# DDR4_SODIMM2.net
KiCad netlist of a schematic drawn in Altium Designer
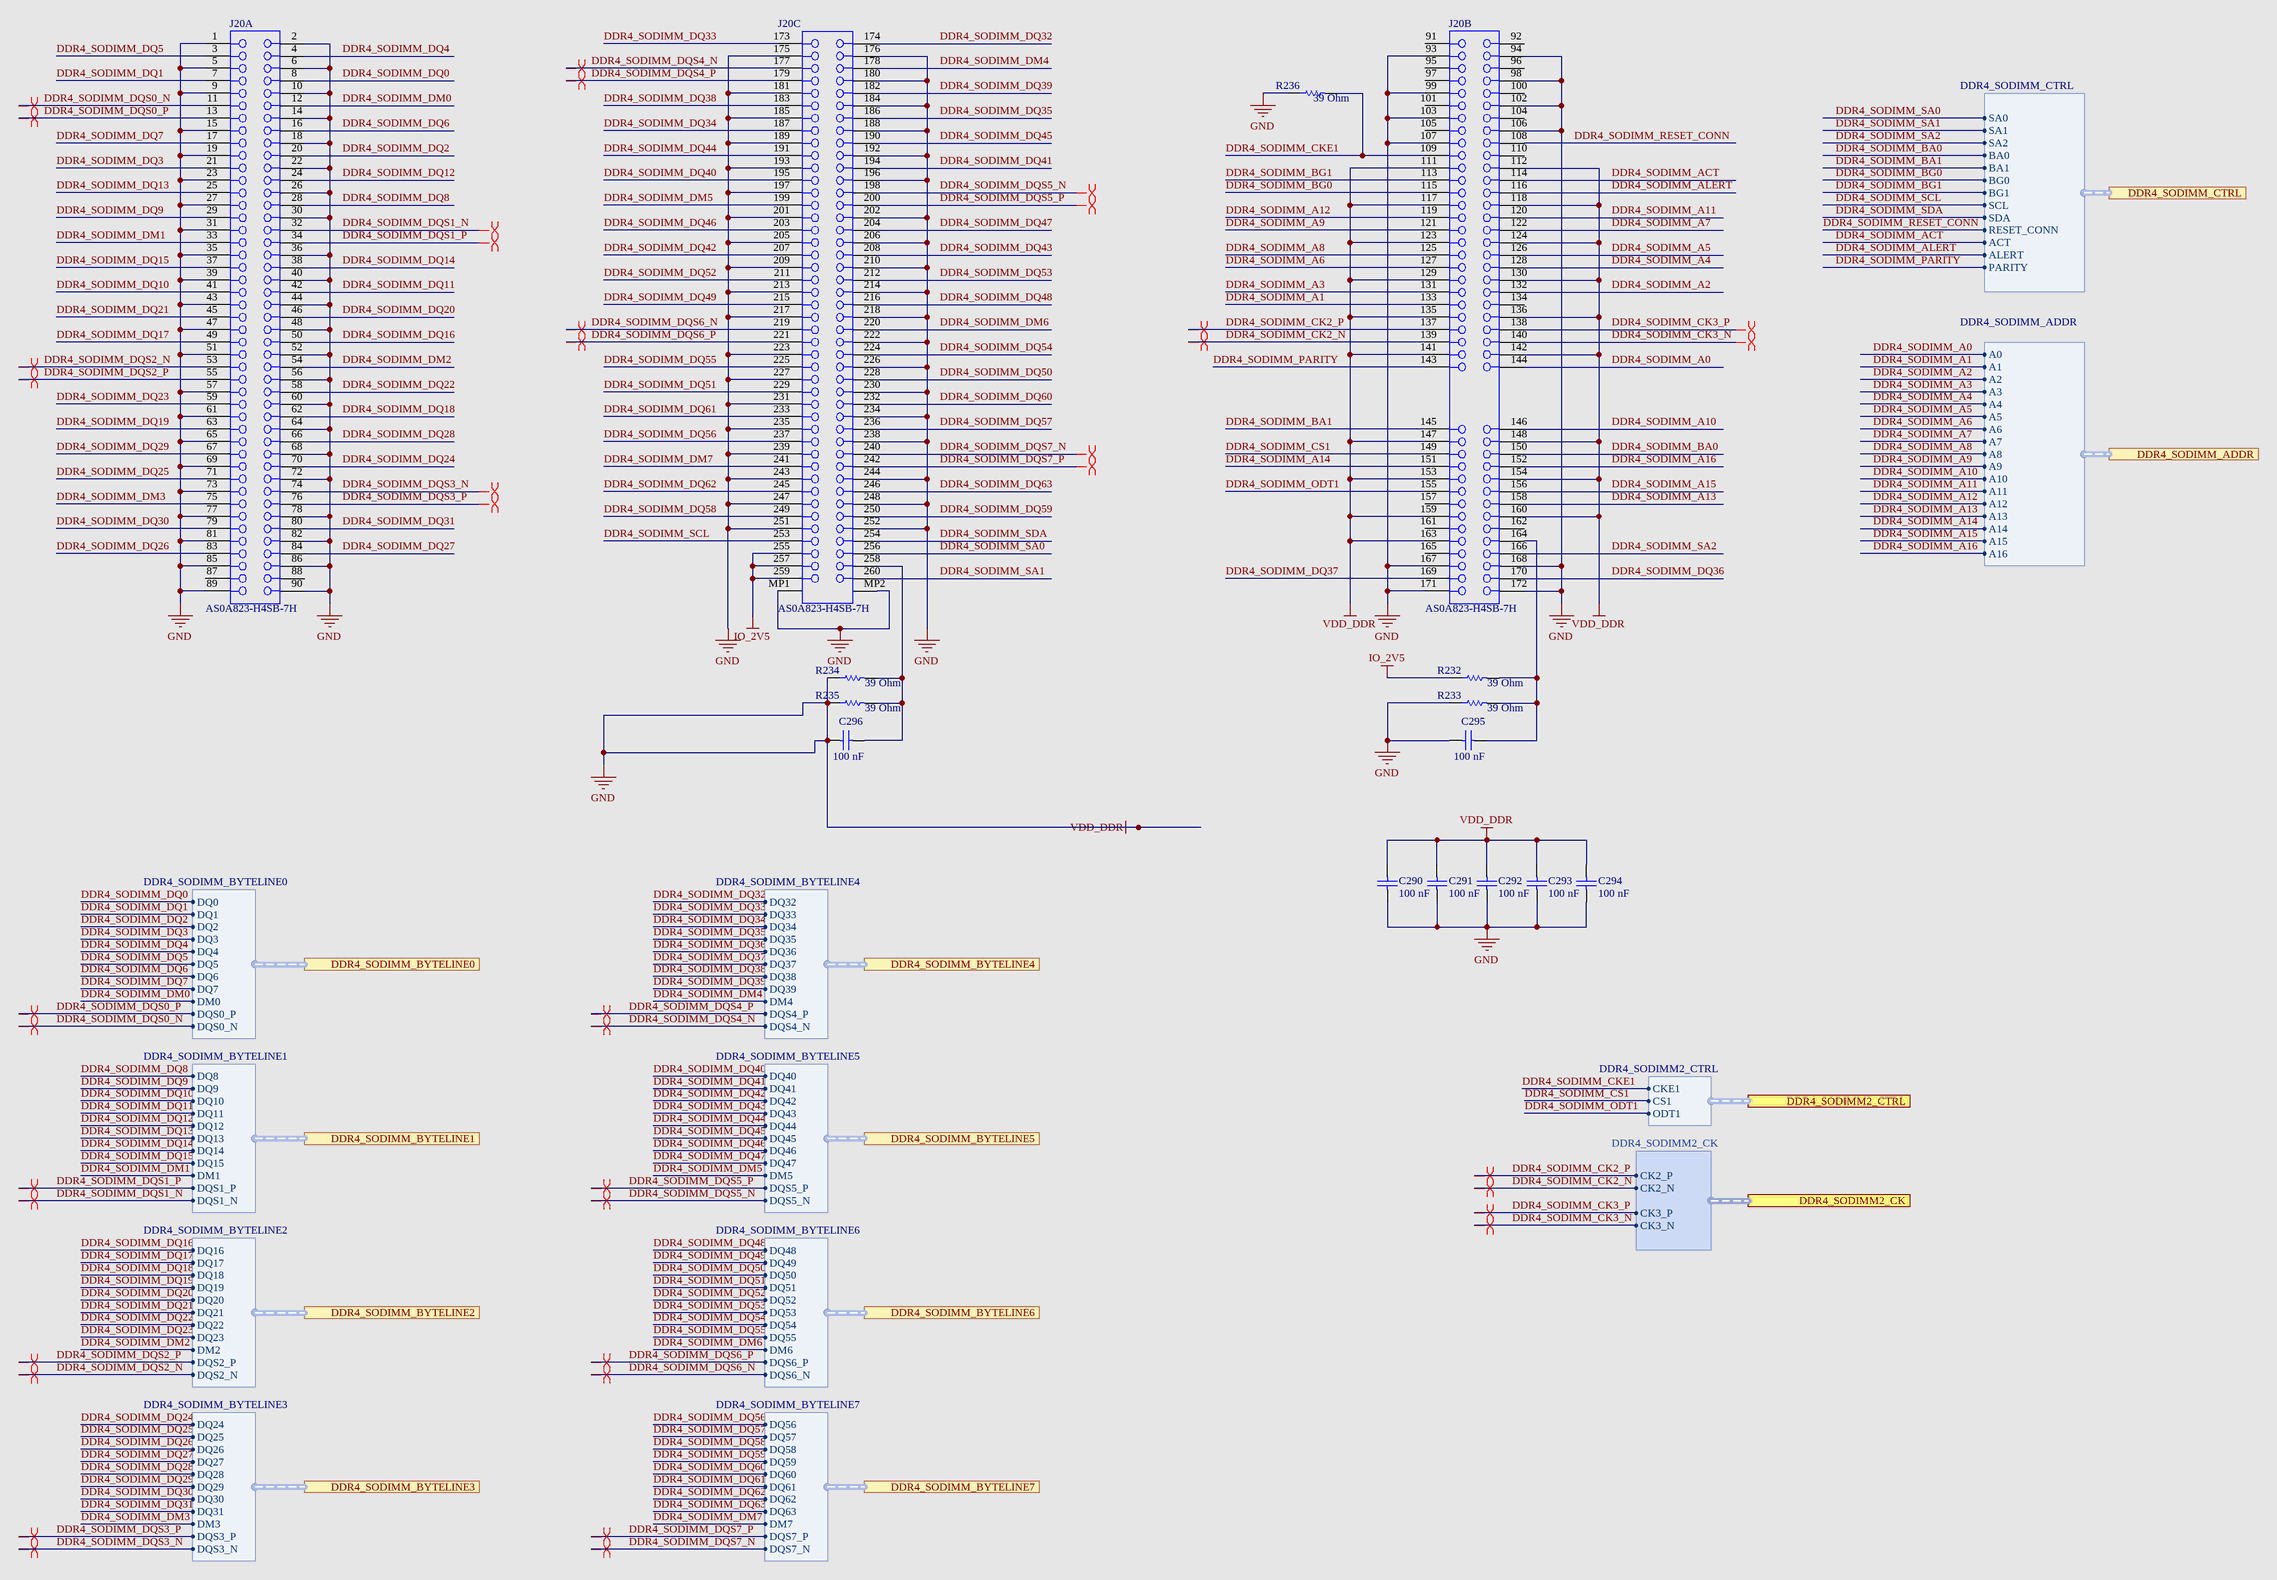
[diagram p0: DDR4_SODIMM2.SchDoc]

(export (version "E")
  (design (tool "Eeschema 10.0.6"))
  (components
    (comp (ref "C290")
      (value "C1005X7R1E104M")
      (footprint "CAPC1005X55X10LL05")
      (description "Chip Capacitor, 0.1 uF, +/- 20%, 25 V, -55 to 125 degC, 0402 (1005 Metric), RoHS, Tape and Reel")
      (fields (field (name "TOLERANCE") "20%") (field (name "CAPACITANCE") "100 nF"))
      (libsource (lib "Altium Content Vault") (part "CAP-NP-2"))
    )
    (comp (ref "C291")
      (value "C1005X7R1E104M")
      (footprint "CAPC1005X55X10LL05")
      (description "Chip Capacitor, 0.1 uF, +/- 20%, 25 V, -55 to 125 degC, 0402 (1005 Metric), RoHS, Tape and Reel")
      (fields (field (name "TOLERANCE") "20%") (field (name "CAPACITANCE") "100 nF"))
      (libsource (lib "Altium Content Vault") (part "CAP-NP-2"))
    )
    (comp (ref "C292")
      (value "C1005X7R1E104M")
      (footprint "CAPC1005X55X10LL05")
      (description "Chip Capacitor, 0.1 uF, +/- 20%, 25 V, -55 to 125 degC, 0402 (1005 Metric), RoHS, Tape and Reel")
      (fields (field (name "TOLERANCE") "20%") (field (name "CAPACITANCE") "100 nF"))
      (libsource (lib "Altium Content Vault") (part "CAP-NP-2"))
    )
    (comp (ref "C293")
      (value "C1005X7R1E104M")
      (footprint "CAPC1005X55X10LL05")
      (description "Chip Capacitor, 0.1 uF, +/- 20%, 25 V, -55 to 125 degC, 0402 (1005 Metric), RoHS, Tape and Reel")
      (fields (field (name "TOLERANCE") "20%") (field (name "CAPACITANCE") "100 nF"))
      (libsource (lib "Altium Content Vault") (part "CAP-NP-2"))
    )
    (comp (ref "C294")
      (value "C1005X7R1E104M")
      (footprint "CAPC1005X55X10LL05")
      (description "Chip Capacitor, 0.1 uF, +/- 20%, 25 V, -55 to 125 degC, 0402 (1005 Metric), RoHS, Tape and Reel")
      (fields (field (name "TOLERANCE") "20%") (field (name "CAPACITANCE") "100 nF"))
      (libsource (lib "Altium Content Vault") (part "CAP-NP-2"))
    )
    (comp (ref "C295")
      (value "C1005X7R1E104M")
      (footprint "CAPC1005X55X10LL05")
      (description "Chip Capacitor, 0.1 uF, +/- 20%, 25 V, -55 to 125 degC, 0402 (1005 Metric), RoHS, Tape and Reel")
      (fields (field (name "TOLERANCE") "20%") (field (name "CAPACITANCE") "100 nF"))
      (libsource (lib "Altium Content Vault") (part "CAP-NP-2"))
    )
    (comp (ref "C296")
      (value "C1005X7R1E104M")
      (footprint "CAPC1005X55X10LL05")
      (description "Chip Capacitor, 0.1 uF, +/- 20%, 25 V, -55 to 125 degC, 0402 (1005 Metric), RoHS, Tape and Reel")
      (fields (field (name "TOLERANCE") "20%") (field (name "CAPACITANCE") "100 nF"))
      (libsource (lib "Altium Content Vault") (part "CAP-NP-2"))
    )
    (comp (ref "J20")
      (value "AS0A823-H4SB-7H")
      (footprint "FOXC-AS0A823-H4SB-7H_V")
      (libsource (lib "Altium Content Vault") (part "CN-2S-2F-R260"))
    )
    (comp (ref "R232")
      (value "NRC04F49R9TRF")
      (footprint "RESC1005X35X25NL8T10")
      (description "Chip Resistor, 39 Ohm, +/- 5%, 0.063 W, -55 to 155 degC, 0402 (1005 Metric), RoHS, Tape and Reel")
      (fields
        (field (name "PARTNUMBER") "RC0402JR-0739RL")
        (field (name "TOLERANCE") "5%")
        (field (name "RESISTANCE") "39 Ohm")
      )
      (libsource (lib "Altium Content Vault") (part "CMP-2002-07994-2"))
    )
    (comp (ref "R233")
      (value "NRC04F49R9TRF")
      (footprint "RESC1005X35X25NL8T10")
      (description "Chip Resistor, 39 Ohm, +/- 5%, 0.063 W, -55 to 155 degC, 0402 (1005 Metric), RoHS, Tape and Reel")
      (fields
        (field (name "PARTNUMBER") "RC0402JR-0739RL")
        (field (name "TOLERANCE") "5%")
        (field (name "RESISTANCE") "39 Ohm")
      )
      (libsource (lib "Altium Content Vault") (part "CMP-2002-07994-2"))
    )
    (comp (ref "R234")
      (value "NRC04F49R9TRF")
      (footprint "RESC1005X35X25NL8T10")
      (description "Chip Resistor, 39 Ohm, +/- 5%, 0.063 W, -55 to 155 degC, 0402 (1005 Metric), RoHS, Tape and Reel")
      (fields
        (field (name "PARTNUMBER") "RC0402JR-0739RL")
        (field (name "TOLERANCE") "5%")
        (field (name "RESISTANCE") "39 Ohm")
      )
      (libsource (lib "Altium Content Vault") (part "CMP-2002-07994-2"))
    )
    (comp (ref "R235")
      (value "NRC04F49R9TRF")
      (footprint "RESC1005X35X25NL8T10")
      (description "Chip Resistor, 39 Ohm, +/- 5%, 0.063 W, -55 to 155 degC, 0402 (1005 Metric), RoHS, Tape and Reel")
      (fields
        (field (name "PARTNUMBER") "RC0402JR-0739RL")
        (field (name "TOLERANCE") "5%")
        (field (name "RESISTANCE") "39 Ohm")
      )
      (libsource (lib "Altium Content Vault") (part "CMP-2002-07994-2"))
    )
    (comp (ref "R236")
      (value "RC0402JR-0739RL")
      (footprint "RESC1005X40X25NL5T10")
      (description "Chip Resistor, 39 Ohm, +/- 5%, 0.063 W, -55 to 155 degC, 0402 (1005 Metric), RoHS, Tape and Reel")
      (fields (field (name "TOLERANCE") "5%") (field (name "RESISTANCE") "39 Ohm"))
      (libsource (lib "Altium Content Vault") (part "CMP-2002-07994-2"))
    )
  )
  (nets
    (net (code "13") (name "/DDR4_SODIMM_A0") (class "Default")
      (node (ref "J20") (pin "144") (pinfunction "144_144") (pintype "passive"))
    )
    (net (code "14") (name "/DDR4_SODIMM_A1") (class "Default")
      (node (ref "J20") (pin "133") (pinfunction "133_133") (pintype "passive"))
    )
    (net (code "15") (name "/DDR4_SODIMM_A2") (class "Default")
      (node (ref "J20") (pin "132") (pinfunction "132_132") (pintype "passive"))
    )
    (net (code "16") (name "/DDR4_SODIMM_A3") (class "Default")
      (node (ref "J20") (pin "131") (pinfunction "131_131") (pintype "passive"))
    )
    (net (code "17") (name "/DDR4_SODIMM_A4") (class "Default")
      (node (ref "J20") (pin "128") (pinfunction "128_128") (pintype "passive"))
    )
    (net (code "18") (name "/DDR4_SODIMM_A5") (class "Default")
      (node (ref "J20") (pin "126") (pinfunction "126_126") (pintype "passive"))
    )
    (net (code "19") (name "/DDR4_SODIMM_A6") (class "Default")
      (node (ref "J20") (pin "127") (pinfunction "127_127") (pintype "passive"))
    )
    (net (code "20") (name "/DDR4_SODIMM_A7") (class "Default")
      (node (ref "J20") (pin "122") (pinfunction "122_122") (pintype "passive"))
    )
    (net (code "21") (name "/DDR4_SODIMM_A8") (class "Default")
      (node (ref "J20") (pin "125") (pinfunction "125_125") (pintype "passive"))
    )
    (net (code "22") (name "/DDR4_SODIMM_A9") (class "Default")
      (node (ref "J20") (pin "121") (pinfunction "121_121") (pintype "passive"))
    )
    (net (code "23") (name "/DDR4_SODIMM_A10") (class "Default")
      (node (ref "J20") (pin "146") (pinfunction "146_146") (pintype "passive"))
    )
    (net (code "24") (name "/DDR4_SODIMM_A11") (class "Default")
      (node (ref "J20") (pin "120") (pinfunction "120_120") (pintype "passive"))
    )
    (net (code "25") (name "/DDR4_SODIMM_A12") (class "Default")
      (node (ref "J20") (pin "119") (pinfunction "119_119") (pintype "passive"))
    )
    (net (code "26") (name "/DDR4_SODIMM_A13") (class "Default")
      (node (ref "J20") (pin "158") (pinfunction "158_158") (pintype "passive"))
    )
    (net (code "27") (name "/DDR4_SODIMM_A14") (class "Default")
      (node (ref "J20") (pin "151") (pinfunction "151_151") (pintype "passive"))
    )
    (net (code "28") (name "/DDR4_SODIMM_A15") (class "Default")
      (node (ref "J20") (pin "156") (pinfunction "156_156") (pintype "passive"))
    )
    (net (code "29") (name "/DDR4_SODIMM_A16") (class "Default")
      (node (ref "J20") (pin "152") (pinfunction "152_152") (pintype "passive"))
    )
    (net (code "30") (name "/DDR4_SODIMM_ACT") (class "Default")
      (node (ref "J20") (pin "114") (pinfunction "114_114") (pintype "passive"))
    )
    (net (code "31") (name "/DDR4_SODIMM_ALERT") (class "Default")
      (node (ref "J20") (pin "116") (pinfunction "116_116") (pintype "passive"))
    )
    (net (code "32") (name "/DDR4_SODIMM_BA0") (class "Default")
      (node (ref "J20") (pin "150") (pinfunction "150_150") (pintype "passive"))
    )
    (net (code "33") (name "/DDR4_SODIMM_BA1") (class "Default")
      (node (ref "J20") (pin "145") (pinfunction "145_145") (pintype "passive"))
    )
    (net (code "34") (name "/DDR4_SODIMM_BG0") (class "Default")
      (node (ref "J20") (pin "115") (pinfunction "115_115") (pintype "passive"))
    )
    (net (code "35") (name "/DDR4_SODIMM_BG1") (class "Default")
      (node (ref "J20") (pin "113") (pinfunction "113_113") (pintype "passive"))
    )
    (net (code "36") (name "/DDR4_SODIMM_CK2_N") (class "Default")
      (node (ref "J20") (pin "139") (pinfunction "139_139") (pintype "passive"))
    )
    (net (code "37") (name "/DDR4_SODIMM_CK2_P") (class "Default")
      (node (ref "J20") (pin "137") (pinfunction "137_137") (pintype "passive"))
    )
    (net (code "38") (name "/DDR4_SODIMM_CK3_N") (class "Default")
      (node (ref "J20") (pin "140") (pinfunction "140_140") (pintype "passive"))
    )
    (net (code "39") (name "/DDR4_SODIMM_CK3_P") (class "Default")
      (node (ref "J20") (pin "138") (pinfunction "138_138") (pintype "passive"))
    )
    (net (code "40") (name "/DDR4_SODIMM_CKE1") (class "Default")
      (node (ref "J20") (pin "109") (pinfunction "109_109") (pintype "passive"))
      (node (ref "R236") (pin "2") (pinfunction "2_2") (pintype "passive"))
    )
    (net (code "41") (name "/DDR4_SODIMM_CS1") (class "Default")
      (node (ref "J20") (pin "149") (pinfunction "149_149") (pintype "passive"))
    )
    (net (code "42") (name "/DDR4_SODIMM_DM0") (class "Default")
      (node (ref "J20") (pin "12") (pinfunction "12_12") (pintype "passive"))
    )
    (net (code "43") (name "/DDR4_SODIMM_DM1") (class "Default")
      (node (ref "J20") (pin "33") (pinfunction "33_33") (pintype "passive"))
    )
    (net (code "44") (name "/DDR4_SODIMM_DM2") (class "Default")
      (node (ref "J20") (pin "54") (pinfunction "54_54") (pintype "passive"))
    )
    (net (code "45") (name "/DDR4_SODIMM_DM3") (class "Default")
      (node (ref "J20") (pin "75") (pinfunction "75_75") (pintype "passive"))
    )
    (net (code "46") (name "/DDR4_SODIMM_DM4") (class "Default")
      (node (ref "J20") (pin "178") (pinfunction "178_178") (pintype "passive"))
    )
    (net (code "47") (name "/DDR4_SODIMM_DM5") (class "Default")
      (node (ref "J20") (pin "199") (pinfunction "199_199") (pintype "passive"))
    )
    (net (code "48") (name "/DDR4_SODIMM_DM6") (class "Default")
      (node (ref "J20") (pin "220") (pinfunction "220_220") (pintype "passive"))
    )
    (net (code "49") (name "/DDR4_SODIMM_DM7") (class "Default")
      (node (ref "J20") (pin "241") (pinfunction "241_241") (pintype "passive"))
    )
    (net (code "50") (name "/DDR4_SODIMM_DQ0") (class "Default")
      (node (ref "J20") (pin "8") (pinfunction "8_8") (pintype "passive"))
    )
    (net (code "51") (name "/DDR4_SODIMM_DQ1") (class "Default")
      (node (ref "J20") (pin "7") (pinfunction "7_7") (pintype "passive"))
    )
    (net (code "52") (name "/DDR4_SODIMM_DQ2") (class "Default")
      (node (ref "J20") (pin "20") (pinfunction "20_20") (pintype "passive"))
    )
    (net (code "53") (name "/DDR4_SODIMM_DQ3") (class "Default")
      (node (ref "J20") (pin "21") (pinfunction "21_21") (pintype "passive"))
    )
    (net (code "54") (name "/DDR4_SODIMM_DQ4") (class "Default")
      (node (ref "J20") (pin "4") (pinfunction "4_4") (pintype "passive"))
    )
    (net (code "55") (name "/DDR4_SODIMM_DQ5") (class "Default")
      (node (ref "J20") (pin "3") (pinfunction "3_3") (pintype "passive"))
    )
    (net (code "56") (name "/DDR4_SODIMM_DQ6") (class "Default")
      (node (ref "J20") (pin "16") (pinfunction "16_16") (pintype "passive"))
    )
    (net (code "57") (name "/DDR4_SODIMM_DQ7") (class "Default")
      (node (ref "J20") (pin "17") (pinfunction "17_17") (pintype "passive"))
    )
    (net (code "58") (name "/DDR4_SODIMM_DQ8") (class "Default")
      (node (ref "J20") (pin "28") (pinfunction "28_28") (pintype "passive"))
    )
    (net (code "59") (name "/DDR4_SODIMM_DQ9") (class "Default")
      (node (ref "J20") (pin "29") (pinfunction "29_29") (pintype "passive"))
    )
    (net (code "60") (name "/DDR4_SODIMM_DQ10") (class "Default")
      (node (ref "J20") (pin "41") (pinfunction "41_41") (pintype "passive"))
    )
    (net (code "61") (name "/DDR4_SODIMM_DQ11") (class "Default")
      (node (ref "J20") (pin "42") (pinfunction "42_42") (pintype "passive"))
    )
    (net (code "62") (name "/DDR4_SODIMM_DQ12") (class "Default")
      (node (ref "J20") (pin "24") (pinfunction "24_24") (pintype "passive"))
    )
    (net (code "63") (name "/DDR4_SODIMM_DQ13") (class "Default")
      (node (ref "J20") (pin "25") (pinfunction "25_25") (pintype "passive"))
    )
    (net (code "64") (name "/DDR4_SODIMM_DQ14") (class "Default")
      (node (ref "J20") (pin "38") (pinfunction "38_38") (pintype "passive"))
    )
    (net (code "65") (name "/DDR4_SODIMM_DQ15") (class "Default")
      (node (ref "J20") (pin "37") (pinfunction "37_37") (pintype "passive"))
    )
    (net (code "66") (name "/DDR4_SODIMM_DQ16") (class "Default")
      (node (ref "J20") (pin "50") (pinfunction "50_50") (pintype "passive"))
    )
    (net (code "67") (name "/DDR4_SODIMM_DQ17") (class "Default")
      (node (ref "J20") (pin "49") (pinfunction "49_49") (pintype "passive"))
    )
    (net (code "68") (name "/DDR4_SODIMM_DQ18") (class "Default")
      (node (ref "J20") (pin "62") (pinfunction "62_62") (pintype "passive"))
    )
    (net (code "69") (name "/DDR4_SODIMM_DQ19") (class "Default")
      (node (ref "J20") (pin "63") (pinfunction "63_63") (pintype "passive"))
    )
    (net (code "70") (name "/DDR4_SODIMM_DQ20") (class "Default")
      (node (ref "J20") (pin "46") (pinfunction "46_46") (pintype "passive"))
    )
    (net (code "71") (name "/DDR4_SODIMM_DQ21") (class "Default")
      (node (ref "J20") (pin "45") (pinfunction "45_45") (pintype "passive"))
    )
    (net (code "72") (name "/DDR4_SODIMM_DQ22") (class "Default")
      (node (ref "J20") (pin "58") (pinfunction "58_58") (pintype "passive"))
    )
    (net (code "73") (name "/DDR4_SODIMM_DQ23") (class "Default")
      (node (ref "J20") (pin "59") (pinfunction "59_59") (pintype "passive"))
    )
    (net (code "74") (name "/DDR4_SODIMM_DQ24") (class "Default")
      (node (ref "J20") (pin "70") (pinfunction "70_70") (pintype "passive"))
    )
    (net (code "75") (name "/DDR4_SODIMM_DQ25") (class "Default")
      (node (ref "J20") (pin "71") (pinfunction "71_71") (pintype "passive"))
    )
    (net (code "76") (name "/DDR4_SODIMM_DQ26") (class "Default")
      (node (ref "J20") (pin "83") (pinfunction "83_83") (pintype "passive"))
    )
    (net (code "77") (name "/DDR4_SODIMM_DQ27") (class "Default")
      (node (ref "J20") (pin "84") (pinfunction "84_84") (pintype "passive"))
    )
    (net (code "78") (name "/DDR4_SODIMM_DQ28") (class "Default")
      (node (ref "J20") (pin "66") (pinfunction "66_66") (pintype "passive"))
    )
    (net (code "79") (name "/DDR4_SODIMM_DQ29") (class "Default")
      (node (ref "J20") (pin "67") (pinfunction "67_67") (pintype "passive"))
    )
    (net (code "80") (name "/DDR4_SODIMM_DQ30") (class "Default")
      (node (ref "J20") (pin "79") (pinfunction "79_79") (pintype "passive"))
    )
    (net (code "81") (name "/DDR4_SODIMM_DQ31") (class "Default")
      (node (ref "J20") (pin "80") (pinfunction "80_80") (pintype "passive"))
    )
    (net (code "82") (name "/DDR4_SODIMM_DQ32") (class "Default")
      (node (ref "J20") (pin "174") (pinfunction "174_174") (pintype "passive"))
    )
    (net (code "83") (name "/DDR4_SODIMM_DQ33") (class "Default")
      (node (ref "J20") (pin "173") (pinfunction "173_173") (pintype "passive"))
    )
    (net (code "84") (name "/DDR4_SODIMM_DQ34") (class "Default")
      (node (ref "J20") (pin "187") (pinfunction "187_187") (pintype "passive"))
    )
    (net (code "85") (name "/DDR4_SODIMM_DQ35") (class "Default")
      (node (ref "J20") (pin "186") (pinfunction "186_186") (pintype "passive"))
    )
    (net (code "86") (name "/DDR4_SODIMM_DQ36") (class "Default")
      (node (ref "J20") (pin "170") (pinfunction "170_170") (pintype "passive"))
    )
    (net (code "87") (name "/DDR4_SODIMM_DQ37") (class "Default")
      (node (ref "J20") (pin "169") (pinfunction "169_169") (pintype "passive"))
    )
    (net (code "88") (name "/DDR4_SODIMM_DQ38") (class "Default")
      (node (ref "J20") (pin "183") (pinfunction "183_183") (pintype "passive"))
    )
    (net (code "89") (name "/DDR4_SODIMM_DQ39") (class "Default")
      (node (ref "J20") (pin "182") (pinfunction "182_182") (pintype "passive"))
    )
    (net (code "90") (name "/DDR4_SODIMM_DQ40") (class "Default")
      (node (ref "J20") (pin "195") (pinfunction "195_195") (pintype "passive"))
    )
    (net (code "91") (name "/DDR4_SODIMM_DQ41") (class "Default")
      (node (ref "J20") (pin "194") (pinfunction "194_194") (pintype "passive"))
    )
    (net (code "92") (name "/DDR4_SODIMM_DQ42") (class "Default")
      (node (ref "J20") (pin "207") (pinfunction "207_207") (pintype "passive"))
    )
    (net (code "93") (name "/DDR4_SODIMM_DQ43") (class "Default")
      (node (ref "J20") (pin "208") (pinfunction "208_208") (pintype "passive"))
    )
    (net (code "94") (name "/DDR4_SODIMM_DQ44") (class "Default")
      (node (ref "J20") (pin "191") (pinfunction "191_191") (pintype "passive"))
    )
    (net (code "95") (name "/DDR4_SODIMM_DQ45") (class "Default")
      (node (ref "J20") (pin "190") (pinfunction "190_190") (pintype "passive"))
    )
    (net (code "96") (name "/DDR4_SODIMM_DQ46") (class "Default")
      (node (ref "J20") (pin "203") (pinfunction "203_203") (pintype "passive"))
    )
    (net (code "97") (name "/DDR4_SODIMM_DQ47") (class "Default")
      (node (ref "J20") (pin "204") (pinfunction "204_204") (pintype "passive"))
    )
    (net (code "98") (name "/DDR4_SODIMM_DQ48") (class "Default")
      (node (ref "J20") (pin "216") (pinfunction "216_216") (pintype "passive"))
    )
    (net (code "99") (name "/DDR4_SODIMM_DQ49") (class "Default")
      (node (ref "J20") (pin "215") (pinfunction "215_215") (pintype "passive"))
    )
    (net (code "100") (name "/DDR4_SODIMM_DQ50") (class "Default")
      (node (ref "J20") (pin "228") (pinfunction "228_228") (pintype "passive"))
    )
    (net (code "101") (name "/DDR4_SODIMM_DQ51") (class "Default")
      (node (ref "J20") (pin "229") (pinfunction "229_229") (pintype "passive"))
    )
    (net (code "102") (name "/DDR4_SODIMM_DQ52") (class "Default")
      (node (ref "J20") (pin "211") (pinfunction "211_211") (pintype "passive"))
    )
    (net (code "103") (name "/DDR4_SODIMM_DQ53") (class "Default")
      (node (ref "J20") (pin "212") (pinfunction "212_212") (pintype "passive"))
    )
    (net (code "104") (name "/DDR4_SODIMM_DQ54") (class "Default")
      (node (ref "J20") (pin "224") (pinfunction "224_224") (pintype "passive"))
    )
    (net (code "105") (name "/DDR4_SODIMM_DQ55") (class "Default")
      (node (ref "J20") (pin "225") (pinfunction "225_225") (pintype "passive"))
    )
    (net (code "106") (name "/DDR4_SODIMM_DQ56") (class "Default")
      (node (ref "J20") (pin "237") (pinfunction "237_237") (pintype "passive"))
    )
    (net (code "107") (name "/DDR4_SODIMM_DQ57") (class "Default")
      (node (ref "J20") (pin "236") (pinfunction "236_236") (pintype "passive"))
    )
    (net (code "108") (name "/DDR4_SODIMM_DQ58") (class "Default")
      (node (ref "J20") (pin "249") (pinfunction "249_249") (pintype "passive"))
    )
    (net (code "109") (name "/DDR4_SODIMM_DQ59") (class "Default")
      (node (ref "J20") (pin "250") (pinfunction "250_250") (pintype "passive"))
    )
    (net (code "110") (name "/DDR4_SODIMM_DQ60") (class "Default")
      (node (ref "J20") (pin "232") (pinfunction "232_232") (pintype "passive"))
    )
    (net (code "111") (name "/DDR4_SODIMM_DQ61") (class "Default")
      (node (ref "J20") (pin "233") (pinfunction "233_233") (pintype "passive"))
    )
    (net (code "112") (name "/DDR4_SODIMM_DQ62") (class "Default")
      (node (ref "J20") (pin "245") (pinfunction "245_245") (pintype "passive"))
    )
    (net (code "113") (name "/DDR4_SODIMM_DQ63") (class "Default")
      (node (ref "J20") (pin "246") (pinfunction "246_246") (pintype "passive"))
    )
    (net (code "114") (name "/DDR4_SODIMM_DQS0_N") (class "Default")
      (node (ref "J20") (pin "11") (pinfunction "11_11") (pintype "passive"))
    )
    (net (code "115") (name "/DDR4_SODIMM_DQS0_P") (class "Default")
      (node (ref "J20") (pin "13") (pinfunction "13_13") (pintype "passive"))
    )
    (net (code "116") (name "/DDR4_SODIMM_DQS1_N") (class "Default")
      (node (ref "J20") (pin "32") (pinfunction "32_32") (pintype "passive"))
    )
    (net (code "117") (name "/DDR4_SODIMM_DQS1_P") (class "Default")
      (node (ref "J20") (pin "34") (pinfunction "34_34") (pintype "passive"))
    )
    (net (code "118") (name "/DDR4_SODIMM_DQS2_N") (class "Default")
      (node (ref "J20") (pin "53") (pinfunction "53_53") (pintype "passive"))
    )
    (net (code "119") (name "/DDR4_SODIMM_DQS2_P") (class "Default")
      (node (ref "J20") (pin "55") (pinfunction "55_55") (pintype "passive"))
    )
    (net (code "120") (name "/DDR4_SODIMM_DQS3_N") (class "Default")
      (node (ref "J20") (pin "74") (pinfunction "74_74") (pintype "passive"))
    )
    (net (code "121") (name "/DDR4_SODIMM_DQS3_P") (class "Default")
      (node (ref "J20") (pin "76") (pinfunction "76_76") (pintype "passive"))
    )
    (net (code "122") (name "/DDR4_SODIMM_DQS4_N") (class "Default")
      (node (ref "J20") (pin "177") (pinfunction "177_177") (pintype "passive"))
    )
    (net (code "123") (name "/DDR4_SODIMM_DQS4_P") (class "Default")
      (node (ref "J20") (pin "179") (pinfunction "179_179") (pintype "passive"))
    )
    (net (code "124") (name "/DDR4_SODIMM_DQS5_N") (class "Default")
      (node (ref "J20") (pin "198") (pinfunction "198_198") (pintype "passive"))
    )
    (net (code "125") (name "/DDR4_SODIMM_DQS5_P") (class "Default")
      (node (ref "J20") (pin "200") (pinfunction "200_200") (pintype "passive"))
    )
    (net (code "126") (name "/DDR4_SODIMM_DQS6_N") (class "Default")
      (node (ref "J20") (pin "219") (pinfunction "219_219") (pintype "passive"))
    )
    (net (code "127") (name "/DDR4_SODIMM_DQS6_P") (class "Default")
      (node (ref "J20") (pin "221") (pinfunction "221_221") (pintype "passive"))
    )
    (net (code "128") (name "/DDR4_SODIMM_DQS7_N") (class "Default")
      (node (ref "J20") (pin "240") (pinfunction "240_240") (pintype "passive"))
    )
    (net (code "129") (name "/DDR4_SODIMM_DQS7_P") (class "Default")
      (node (ref "J20") (pin "242") (pinfunction "242_242") (pintype "passive"))
    )
    (net (code "130") (name "/DDR4_SODIMM_ODT1") (class "Default")
      (node (ref "J20") (pin "155") (pinfunction "155_155") (pintype "passive"))
    )
    (net (code "131") (name "/DDR4_SODIMM_PARITY") (class "Default")
      (node (ref "J20") (pin "143") (pinfunction "143_143") (pintype "passive"))
    )
    (net (code "132") (name "/DDR4_SODIMM_RESET_CONN") (class "Default")
      (node (ref "J20") (pin "108") (pinfunction "108_108") (pintype "passive"))
    )
    (net (code "133") (name "/DDR4_SODIMM_SA0") (class "Default")
      (node (ref "J20") (pin "256") (pinfunction "256_256") (pintype "passive"))
    )
    (net (code "134") (name "/DDR4_SODIMM_SA1") (class "Default")
      (node (ref "J20") (pin "260") (pinfunction "260_260") (pintype "passive"))
    )
    (net (code "135") (name "/DDR4_SODIMM_SA2") (class "Default")
      (node (ref "J20") (pin "166") (pinfunction "166_166") (pintype "passive"))
    )
    (net (code "136") (name "/DDR4_SODIMM_SCL") (class "Default")
      (node (ref "J20") (pin "253") (pinfunction "253_253") (pintype "passive"))
    )
    (net (code "137") (name "/DDR4_SODIMM_SDA") (class "Default")
      (node (ref "J20") (pin "254") (pinfunction "254_254") (pintype "passive"))
    )
    (net (code "150") (name "GND") (class "Default")
      (node (ref "C290") (pin "1") (pinfunction "1_1") (pintype "passive"))
      (node (ref "C290") (pin "2") (pinfunction "2_2") (pintype "passive"))
      (node (ref "C291") (pin "1") (pinfunction "1_1") (pintype "passive"))
      (node (ref "C291") (pin "2") (pinfunction "2_2") (pintype "passive"))
      (node (ref "C292") (pin "1") (pinfunction "1_1") (pintype "passive"))
      (node (ref "C292") (pin "2") (pinfunction "2_2") (pintype "passive"))
      (node (ref "C293") (pin "1") (pinfunction "1_1") (pintype "passive"))
      (node (ref "C293") (pin "2") (pinfunction "2_2") (pintype "passive"))
      (node (ref "C294") (pin "1") (pinfunction "1_1") (pintype "passive"))
      (node (ref "C294") (pin "2") (pinfunction "2_2") (pintype "passive"))
      (node (ref "C295") (pin "2") (pinfunction "2_2") (pintype "passive"))
      (node (ref "C296") (pin "2") (pinfunction "2_2") (pintype "passive"))
      (node (ref "J20") (pin "1") (pinfunction "1_1") (pintype "passive"))
      (node (ref "J20") (pin "10") (pinfunction "10_10") (pintype "passive"))
      (node (ref "J20") (pin "102") (pinfunction "102_102") (pintype "passive"))
      (node (ref "J20") (pin "103") (pinfunction "103_103") (pintype "passive"))
      (node (ref "J20") (pin "106") (pinfunction "106_106") (pintype "passive"))
      (node (ref "J20") (pin "107") (pinfunction "107_107") (pintype "passive"))
      (node (ref "J20") (pin "111") (pinfunction "111_111") (pintype "passive"))
      (node (ref "J20") (pin "112") (pinfunction "112_112") (pintype "passive"))
      (node (ref "J20") (pin "117") (pinfunction "117_117") (pintype "passive"))
      (node (ref "J20") (pin "118") (pinfunction "118_118") (pintype "passive"))
      (node (ref "J20") (pin "123") (pinfunction "123_123") (pintype "passive"))
      (node (ref "J20") (pin "124") (pinfunction "124_124") (pintype "passive"))
      (node (ref "J20") (pin "129") (pinfunction "129_129") (pintype "passive"))
      (node (ref "J20") (pin "130") (pinfunction "130_130") (pintype "passive"))
      (node (ref "J20") (pin "135") (pinfunction "135_135") (pintype "passive"))
      (node (ref "J20") (pin "136") (pinfunction "136_136") (pintype "passive"))
      (node (ref "J20") (pin "14") (pinfunction "14_14") (pintype "passive"))
      (node (ref "J20") (pin "141") (pinfunction "141_141") (pintype "passive"))
      (node (ref "J20") (pin "142") (pinfunction "142_142") (pintype "passive"))
      (node (ref "J20") (pin "147") (pinfunction "147_147") (pintype "passive"))
      (node (ref "J20") (pin "148") (pinfunction "148_148") (pintype "passive"))
      (node (ref "J20") (pin "15") (pinfunction "15_15") (pintype "passive"))
      (node (ref "J20") (pin "153") (pinfunction "153_153") (pintype "passive"))
      (node (ref "J20") (pin "154") (pinfunction "154_154") (pintype "passive"))
      (node (ref "J20") (pin "159") (pinfunction "159_159") (pintype "passive"))
      (node (ref "J20") (pin "160") (pinfunction "160_160") (pintype "passive"))
      (node (ref "J20") (pin "163") (pinfunction "163_163") (pintype "passive"))
      (node (ref "J20") (pin "167") (pinfunction "167_167") (pintype "passive"))
      (node (ref "J20") (pin "168") (pinfunction "168_168") (pintype "passive"))
      (node (ref "J20") (pin "171") (pinfunction "171_171") (pintype "passive"))
      (node (ref "J20") (pin "172") (pinfunction "172_172") (pintype "passive"))
      (node (ref "J20") (pin "175") (pinfunction "175_175") (pintype "passive"))
      (node (ref "J20") (pin "176") (pinfunction "176_176") (pintype "passive"))
      (node (ref "J20") (pin "18") (pinfunction "18_18") (pintype "passive"))
      (node (ref "J20") (pin "180") (pinfunction "180_180") (pintype "passive"))
      (node (ref "J20") (pin "181") (pinfunction "181_181") (pintype "passive"))
      (node (ref "J20") (pin "184") (pinfunction "184_184") (pintype "passive"))
      (node (ref "J20") (pin "185") (pinfunction "185_185") (pintype "passive"))
      (node (ref "J20") (pin "188") (pinfunction "188_188") (pintype "passive"))
      (node (ref "J20") (pin "189") (pinfunction "189_189") (pintype "passive"))
      (node (ref "J20") (pin "19") (pinfunction "19_19") (pintype "passive"))
      (node (ref "J20") (pin "192") (pinfunction "192_192") (pintype "passive"))
      (node (ref "J20") (pin "193") (pinfunction "193_193") (pintype "passive"))
      (node (ref "J20") (pin "196") (pinfunction "196_196") (pintype "passive"))
      (node (ref "J20") (pin "197") (pinfunction "197_197") (pintype "passive"))
      (node (ref "J20") (pin "2") (pinfunction "2_2") (pintype "passive"))
      (node (ref "J20") (pin "201") (pinfunction "201_201") (pintype "passive"))
      (node (ref "J20") (pin "202") (pinfunction "202_202") (pintype "passive"))
      (node (ref "J20") (pin "205") (pinfunction "205_205") (pintype "passive"))
      (node (ref "J20") (pin "206") (pinfunction "206_206") (pintype "passive"))
      (node (ref "J20") (pin "209") (pinfunction "209_209") (pintype "passive"))
      (node (ref "J20") (pin "210") (pinfunction "210_210") (pintype "passive"))
      (node (ref "J20") (pin "213") (pinfunction "213_213") (pintype "passive"))
      (node (ref "J20") (pin "214") (pinfunction "214_214") (pintype "passive"))
      (node (ref "J20") (pin "217") (pinfunction "217_217") (pintype "passive"))
      (node (ref "J20") (pin "218") (pinfunction "218_218") (pintype "passive"))
      (node (ref "J20") (pin "22") (pinfunction "22_22") (pintype "passive"))
      (node (ref "J20") (pin "222") (pinfunction "222_222") (pintype "passive"))
      (node (ref "J20") (pin "223") (pinfunction "223_223") (pintype "passive"))
      (node (ref "J20") (pin "226") (pinfunction "226_226") (pintype "passive"))
      (node (ref "J20") (pin "227") (pinfunction "227_227") (pintype "passive"))
      (node (ref "J20") (pin "23") (pinfunction "23_23") (pintype "passive"))
      (node (ref "J20") (pin "230") (pinfunction "230_230") (pintype "passive"))
      (node (ref "J20") (pin "231") (pinfunction "231_231") (pintype "passive"))
      (node (ref "J20") (pin "234") (pinfunction "234_234") (pintype "passive"))
      (node (ref "J20") (pin "235") (pinfunction "235_235") (pintype "passive"))
      (node (ref "J20") (pin "238") (pinfunction "238_238") (pintype "passive"))
      (node (ref "J20") (pin "239") (pinfunction "239_239") (pintype "passive"))
      (node (ref "J20") (pin "243") (pinfunction "243_243") (pintype "passive"))
      (node (ref "J20") (pin "244") (pinfunction "244_244") (pintype "passive"))
      (node (ref "J20") (pin "247") (pinfunction "247_247") (pintype "passive"))
      (node (ref "J20") (pin "248") (pinfunction "248_248") (pintype "passive"))
      (node (ref "J20") (pin "251") (pinfunction "251_251") (pintype "passive"))
      (node (ref "J20") (pin "252") (pinfunction "252_252") (pintype "passive"))
      (node (ref "J20") (pin "26") (pinfunction "26_26") (pintype "passive"))
      (node (ref "J20") (pin "27") (pinfunction "27_27") (pintype "passive"))
      (node (ref "J20") (pin "30") (pinfunction "30_30") (pintype "passive"))
      (node (ref "J20") (pin "31") (pinfunction "31_31") (pintype "passive"))
      (node (ref "J20") (pin "35") (pinfunction "35_35") (pintype "passive"))
      (node (ref "J20") (pin "36") (pinfunction "36_36") (pintype "passive"))
      (node (ref "J20") (pin "39") (pinfunction "39_39") (pintype "passive"))
      (node (ref "J20") (pin "40") (pinfunction "40_40") (pintype "passive"))
      (node (ref "J20") (pin "43") (pinfunction "43_43") (pintype "passive"))
      (node (ref "J20") (pin "44") (pinfunction "44_44") (pintype "passive"))
      (node (ref "J20") (pin "47") (pinfunction "47_47") (pintype "passive"))
      (node (ref "J20") (pin "48") (pinfunction "48_48") (pintype "passive"))
      (node (ref "J20") (pin "5") (pinfunction "5_5") (pintype "passive"))
      (node (ref "J20") (pin "51") (pinfunction "51_51") (pintype "passive"))
      (node (ref "J20") (pin "52") (pinfunction "52_52") (pintype "passive"))
      (node (ref "J20") (pin "56") (pinfunction "56_56") (pintype "passive"))
      (node (ref "J20") (pin "57") (pinfunction "57_57") (pintype "passive"))
      (node (ref "J20") (pin "6") (pinfunction "6_6") (pintype "passive"))
      (node (ref "J20") (pin "60") (pinfunction "60_60") (pintype "passive"))
      (node (ref "J20") (pin "61") (pinfunction "61_61") (pintype "passive"))
      (node (ref "J20") (pin "64") (pinfunction "64_64") (pintype "passive"))
      (node (ref "J20") (pin "65") (pinfunction "65_65") (pintype "passive"))
      (node (ref "J20") (pin "68") (pinfunction "68_68") (pintype "passive"))
      (node (ref "J20") (pin "69") (pinfunction "69_69") (pintype "passive"))
      (node (ref "J20") (pin "72") (pinfunction "72_72") (pintype "passive"))
      (node (ref "J20") (pin "73") (pinfunction "73_73") (pintype "passive"))
      (node (ref "J20") (pin "77") (pinfunction "77_77") (pintype "passive"))
      (node (ref "J20") (pin "78") (pinfunction "78_78") (pintype "passive"))
      (node (ref "J20") (pin "81") (pinfunction "81_81") (pintype "passive"))
      (node (ref "J20") (pin "82") (pinfunction "82_82") (pintype "passive"))
      (node (ref "J20") (pin "85") (pinfunction "85_85") (pintype "passive"))
      (node (ref "J20") (pin "86") (pinfunction "86_86") (pintype "passive"))
      (node (ref "J20") (pin "89") (pinfunction "89_89") (pintype "passive"))
      (node (ref "J20") (pin "9") (pinfunction "9_9") (pintype "passive"))
      (node (ref "J20") (pin "90") (pinfunction "90_90") (pintype "passive"))
      (node (ref "J20") (pin "93") (pinfunction "93_93") (pintype "passive"))
      (node (ref "J20") (pin "94") (pinfunction "94_94") (pintype "passive"))
      (node (ref "J20") (pin "98") (pinfunction "98_98") (pintype "passive"))
      (node (ref "J20") (pin "99") (pinfunction "99_99") (pintype "passive"))
      (node (ref "J20") (pin "MP1") (pinfunction "MP1_MP1") (pintype "passive"))
      (node (ref "J20") (pin "MP2") (pinfunction "MP2_MP2") (pintype "passive"))
      (node (ref "R233") (pin "1") (pinfunction "1_1") (pintype "passive"))
      (node (ref "R234") (pin "1") (pinfunction "1_1") (pintype "passive"))
      (node (ref "R235") (pin "1") (pinfunction "1_1") (pintype "passive"))
      (node (ref "R236") (pin "1") (pinfunction "1_1") (pintype "passive"))
    )
    (net (code "151") (name "IO_2V5") (class "Default")
      (node (ref "J20") (pin "255") (pinfunction "255_255") (pintype "passive"))
      (node (ref "J20") (pin "257") (pinfunction "257_257") (pintype "passive"))
      (node (ref "J20") (pin "259") (pinfunction "259_259") (pintype "passive"))
      (node (ref "R232") (pin "1") (pinfunction "1_1") (pintype "passive"))
    )
    (net (code "152") (name "Net-(C295-Pad1)") (class "Default")
      (node (ref "C295") (pin "1") (pinfunction "1_1") (pintype "passive"))
      (node (ref "J20") (pin "164") (pinfunction "164_164") (pintype "passive"))
      (node (ref "R232") (pin "2") (pinfunction "2_2") (pintype "passive"))
      (node (ref "R233") (pin "2") (pinfunction "2_2") (pintype "passive"))
    )
    (net (code "153") (name "Net-(C296-Pad1)") (class "Default")
      (node (ref "C296") (pin "1") (pinfunction "1_1") (pintype "passive"))
      (node (ref "J20") (pin "258") (pinfunction "258_258") (pintype "passive"))
      (node (ref "R234") (pin "2") (pinfunction "2_2") (pintype "passive"))
      (node (ref "R235") (pin "2") (pinfunction "2_2") (pintype "passive"))
    )
    (net (code "154") (name "unconnected-(J20-Pad87)") (class "Default")
      (node (ref "J20") (pin "87") (pinfunction "87_87") (pintype "passive"))
    )
    (net (code "155") (name "unconnected-(J20-Pad88)") (class "Default")
      (node (ref "J20") (pin "88") (pinfunction "88_88") (pintype "passive"))
    )
    (net (code "156") (name "unconnected-(J20-Pad91)") (class "Default")
      (node (ref "J20") (pin "91") (pinfunction "91_91") (pintype "passive"))
    )
    (net (code "157") (name "unconnected-(J20-Pad92)") (class "Default")
      (node (ref "J20") (pin "92") (pinfunction "92_92") (pintype "passive"))
    )
    (net (code "158") (name "unconnected-(J20-Pad95)") (class "Default")
      (node (ref "J20") (pin "95") (pinfunction "95_95") (pintype "passive"))
    )
    (net (code "159") (name "unconnected-(J20-Pad96)") (class "Default")
      (node (ref "J20") (pin "96") (pinfunction "96_96") (pintype "passive"))
    )
    (net (code "160") (name "unconnected-(J20-Pad97)") (class "Default")
      (node (ref "J20") (pin "97") (pinfunction "97_97") (pintype "passive"))
    )
    (net (code "161") (name "unconnected-(J20-Pad100)") (class "Default")
      (node (ref "J20") (pin "100") (pinfunction "100_100") (pintype "passive"))
    )
    (net (code "162") (name "unconnected-(J20-Pad101)") (class "Default")
      (node (ref "J20") (pin "101") (pinfunction "101_101") (pintype "passive"))
    )
    (net (code "163") (name "unconnected-(J20-Pad104)") (class "Default")
      (node (ref "J20") (pin "104") (pinfunction "104_104") (pintype "passive"))
    )
    (net (code "164") (name "unconnected-(J20-Pad105)") (class "Default")
      (node (ref "J20") (pin "105") (pinfunction "105_105") (pintype "passive"))
    )
    (net (code "165") (name "unconnected-(J20-Pad110)") (class "Default")
      (node (ref "J20") (pin "110") (pinfunction "110_110") (pintype "passive"))
    )
    (net (code "166") (name "unconnected-(J20-Pad134)") (class "Default")
      (node (ref "J20") (pin "134") (pinfunction "134_134") (pintype "passive"))
    )
    (net (code "167") (name "unconnected-(J20-Pad157)") (class "Default")
      (node (ref "J20") (pin "157") (pinfunction "157_157") (pintype "passive"))
    )
    (net (code "168") (name "unconnected-(J20-Pad161)") (class "Default")
      (node (ref "J20") (pin "161") (pinfunction "161_161") (pintype "passive"))
    )
    (net (code "169") (name "unconnected-(J20-Pad162)") (class "Default")
      (node (ref "J20") (pin "162") (pinfunction "162_162") (pintype "passive"))
    )
    (net (code "170") (name "unconnected-(J20-Pad165)") (class "Default")
      (node (ref "J20") (pin "165") (pinfunction "165_165") (pintype "passive"))
    )
  )
)
